# HandschuhPlatineFinal.net
KiCad netlist of a schematic drawn in EAGLE
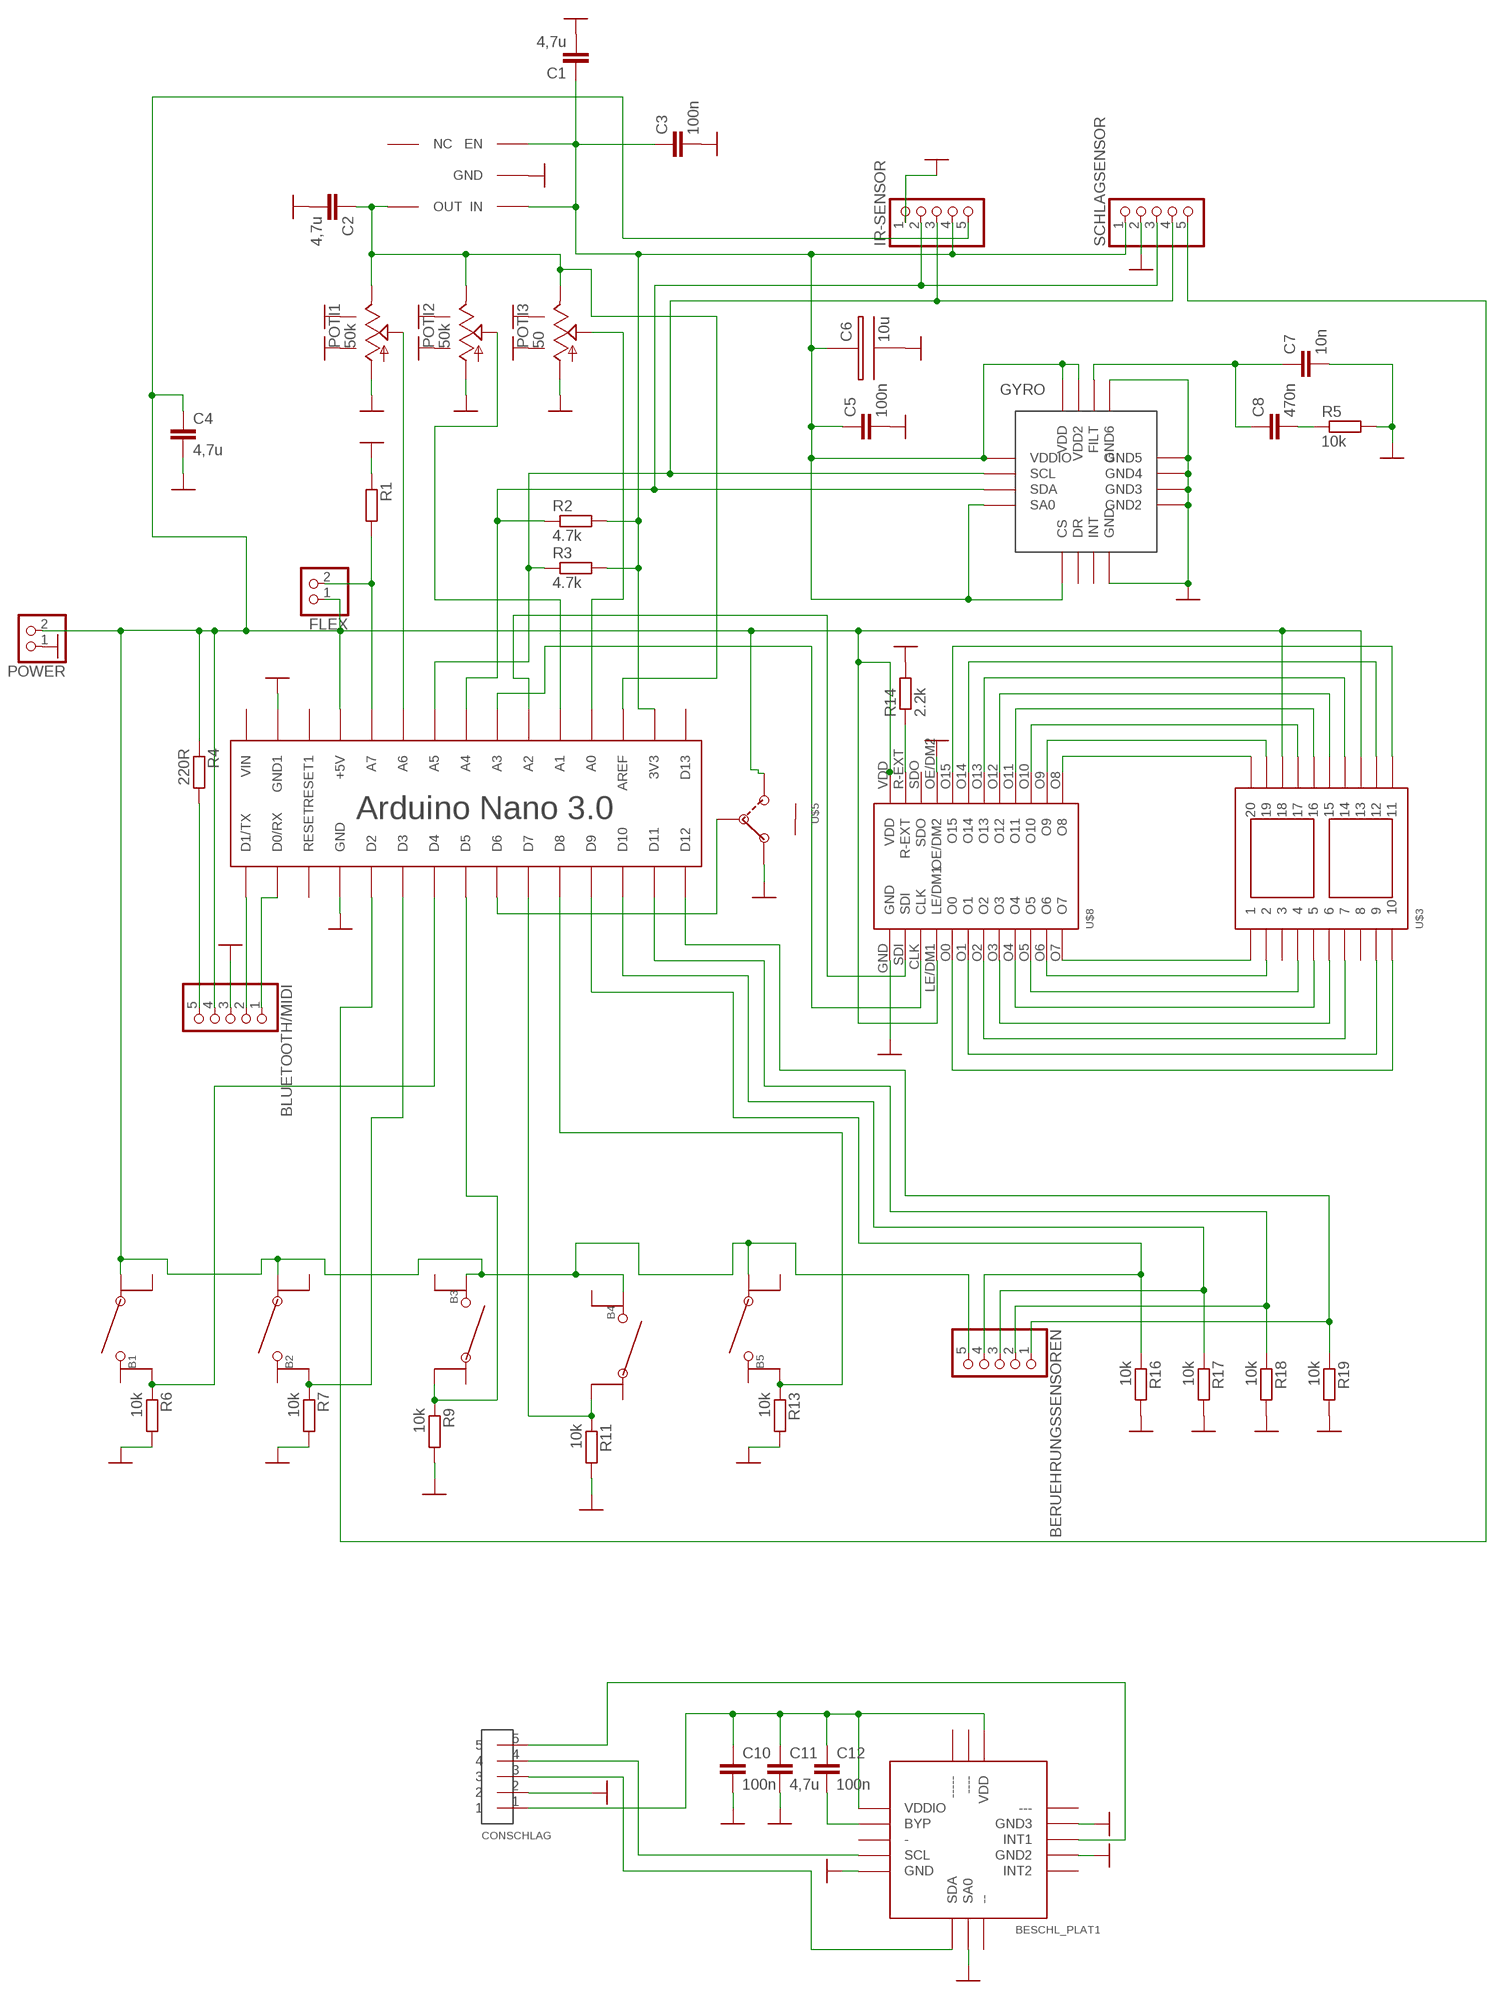
[diagram p0: schematic, sheet 1]

(export (version "E")
  (design (tool "Eeschema 10.0.6"))
  (components
    (comp (ref "B1")
      (value "BUTTON")
      (footprint "eagle-import:BUTTON")
      (libsource (lib "eagle-import") (part "BUTTON"))
    )
    (comp (ref "B2")
      (value "BUTTON")
      (footprint "eagle-import:BUTTON")
      (libsource (lib "eagle-import") (part "BUTTON"))
    )
    (comp (ref "B3")
      (value "BUTTON")
      (footprint "eagle-import:BUTTON")
      (libsource (lib "eagle-import") (part "BUTTON"))
    )
    (comp (ref "B4")
      (value "BUTTON")
      (footprint "eagle-import:BUTTON")
      (libsource (lib "eagle-import") (part "BUTTON"))
    )
    (comp (ref "B5")
      (value "BUTTON")
      (footprint "eagle-import:BUTTON")
      (libsource (lib "eagle-import") (part "BUTTON"))
    )
    (comp (ref "BERUEHRUNGSSENSOREN")
      (value "PINHD-1X5")
      (footprint "eagle-import:1X05")
      (libsource (lib "eagle-import") (part "PINHD-1X5"))
    )
    (comp (ref "BESCHL_PLAT1")
      (value "BESCHLEUNIGSUNGSSENSOR")
      (footprint "eagle-import:BESCHLEUNIGUNGSSENSOR")
      (libsource (lib "eagle-import") (part "BESCHLEUNIGSUNGSSENSOR"))
    )
    (comp (ref "BLUETOOTH/MIDI")
      (value "PINHD-1X5")
      (footprint "eagle-import:1X05")
      (libsource (lib "eagle-import") (part "PINHD-1X5"))
    )
    (comp (ref "C1")
      (value "4,7u")
      (footprint "eagle-import:C0805")
      (libsource (lib "eagle-import") (part "C-EUC0805"))
    )
    (comp (ref "C2")
      (value "4,7u")
      (footprint "eagle-import:C0805")
      (libsource (lib "eagle-import") (part "C-EUC0805"))
    )
    (comp (ref "C3")
      (value "100n")
      (footprint "eagle-import:C0805")
      (libsource (lib "eagle-import") (part "C-EUC0805"))
    )
    (comp (ref "C4")
      (value "4,7u")
      (footprint "eagle-import:C0805")
      (libsource (lib "eagle-import") (part "C-EUC0805"))
    )
    (comp (ref "C5")
      (value "100n")
      (footprint "eagle-import:C0805")
      (libsource (lib "eagle-import") (part "C-EUC0805"))
    )
    (comp (ref "C6")
      (value "10u")
      (footprint "eagle-import:22U-KONDENSATOR")
      (libsource (lib "eagle-import") (part "22U-KONDENSATOR"))
    )
    (comp (ref "C7")
      (value "10n")
      (footprint "eagle-import:C0805")
      (libsource (lib "eagle-import") (part "C-EUC0805"))
    )
    (comp (ref "C8")
      (value "470n")
      (footprint "eagle-import:C0805")
      (libsource (lib "eagle-import") (part "C-EUC0805"))
    )
    (comp (ref "C10")
      (value "100n")
      (footprint "eagle-import:C0805")
      (libsource (lib "eagle-import") (part "C-EUC0805"))
    )
    (comp (ref "C11")
      (value "4,7u")
      (footprint "eagle-import:C0805")
      (libsource (lib "eagle-import") (part "C-EUC0805"))
    )
    (comp (ref "C12")
      (value "100n")
      (footprint "eagle-import:C0805")
      (libsource (lib "eagle-import") (part "C-EUC0805"))
    )
    (comp (ref "CONSCHLAG")
      (value "BREAKBOARDCON2")
      (footprint "eagle-import:BREAKBOARDCON")
      (libsource (lib "eagle-import") (part "BREAKBOARDCON2"))
    )
    (comp (ref "FLEX")
      (value "PINHD-1X2")
      (footprint "eagle-import:1X02")
      (libsource (lib "eagle-import") (part "PINHD-1X2"))
    )
    (comp (ref "GYRO")
      (value "GYRO")
      (footprint "eagle-import:GYRO")
      (libsource (lib "eagle-import") (part "GYRO"))
    )
    (comp (ref "IR-SENSOR")
      (value "PINHD-1X5")
      (footprint "eagle-import:1X05")
      (libsource (lib "eagle-import") (part "PINHD-1X5"))
    )
    (comp (ref "POTI1")
      (value "50k")
      (footprint "eagle-import:POTI")
      (libsource (lib "eagle-import") (part "POTI"))
    )
    (comp (ref "POTI2")
      (value "50k")
      (footprint "eagle-import:POTI")
      (libsource (lib "eagle-import") (part "POTI"))
    )
    (comp (ref "POTI3")
      (value "50")
      (footprint "eagle-import:POTI")
      (libsource (lib "eagle-import") (part "POTI"))
    )
    (comp (ref "POWER")
      (value "PINHD-1X2")
      (footprint "eagle-import:1X02")
      (libsource (lib "eagle-import") (part "PINHD-1X2"))
    )
    (comp (ref "R1")
      (value "R-EU_M0805")
      (footprint "eagle-import:M0805")
      (libsource (lib "eagle-import") (part "R-EU_M0805"))
    )
    (comp (ref "R2")
      (value "4.7k")
      (footprint "eagle-import:M0805")
      (libsource (lib "eagle-import") (part "R-EU_M0805"))
    )
    (comp (ref "R3")
      (value "4.7k")
      (footprint "eagle-import:M0805")
      (libsource (lib "eagle-import") (part "R-EU_M0805"))
    )
    (comp (ref "R4")
      (value "220R")
      (footprint "eagle-import:M0805")
      (libsource (lib "eagle-import") (part "R-EU_M0805"))
    )
    (comp (ref "R5")
      (value "10k")
      (footprint "eagle-import:M0805")
      (libsource (lib "eagle-import") (part "R-EU_M0805"))
    )
    (comp (ref "R6")
      (value "10k")
      (footprint "eagle-import:M0805")
      (libsource (lib "eagle-import") (part "R-EU_M0805"))
    )
    (comp (ref "R7")
      (value "10k")
      (footprint "eagle-import:M0805")
      (libsource (lib "eagle-import") (part "R-EU_M0805"))
    )
    (comp (ref "R9")
      (value "10k")
      (footprint "eagle-import:M0805")
      (libsource (lib "eagle-import") (part "R-EU_M0805"))
    )
    (comp (ref "R11")
      (value "10k")
      (footprint "eagle-import:M0805")
      (libsource (lib "eagle-import") (part "R-EU_M0805"))
    )
    (comp (ref "R13")
      (value "10k")
      (footprint "eagle-import:M0805")
      (libsource (lib "eagle-import") (part "R-EU_M0805"))
    )
    (comp (ref "R14")
      (value "2.2k")
      (footprint "eagle-import:M0805")
      (libsource (lib "eagle-import") (part "R-EU_M0805"))
    )
    (comp (ref "R16")
      (value "10k")
      (footprint "eagle-import:M0805")
      (libsource (lib "eagle-import") (part "R-EU_M0805"))
    )
    (comp (ref "R17")
      (value "10k")
      (footprint "eagle-import:M0805")
      (libsource (lib "eagle-import") (part "R-EU_M0805"))
    )
    (comp (ref "R18")
      (value "10k")
      (footprint "eagle-import:M0805")
      (libsource (lib "eagle-import") (part "R-EU_M0805"))
    )
    (comp (ref "R19")
      (value "10k")
      (footprint "eagle-import:M0805")
      (libsource (lib "eagle-import") (part "R-EU_M0805"))
    )
    (comp (ref "SCHLAGSENSOR")
      (value "PINHD-1X5")
      (footprint "eagle-import:1X05")
      (libsource (lib "eagle-import") (part "PINHD-1X5"))
    )
    (comp (ref "U$2")
      (value "ARDUINONANO")
      (footprint "eagle-import:PDIP-32")
      (libsource (lib "eagle-import") (part "ARDUINONANO"))
    )
    (comp (ref "U$3")
      (value "7-SEGMENT")
      (footprint "eagle-import:7-SEGMENT")
      (libsource (lib "eagle-import") (part "7-SEGMENT"))
    )
    (comp (ref "U$4")
      (value "1,1V-SPANNUNGSREGLER")
      (footprint "eagle-import:1,1V-SPANNUNGSREGLER")
      (libsource (lib "eagle-import") (part "1,1V-SPANNUNGSREGLER"))
    )
    (comp (ref "U$5")
      (value "SCHALTER")
      (footprint "eagle-import:SCHALTER")
      (libsource (lib "eagle-import") (part "SCHALTER"))
    )
    (comp (ref "U$8")
      (value "7-SEGMENT-TREIBER")
      (footprint "eagle-import:7-SEGMENT-TREIBER")
      (libsource (lib "eagle-import") (part "7-SEGMENT-TREIBER"))
    )
  )
  (nets
    (net (code "1") (name "Net-(B1-Pad2)") (class "Default")
      (node (ref "B1") (pin "2") (pinfunction "2_2") (pintype "bidirectional"))
      (node (ref "R6") (pin "1") (pinfunction "1_1") (pintype "passive"))
      (node (ref "U$2") (pin "D4") (pinfunction "D4_D4") (pintype "bidirectional"))
    )
    (net (code "2") (name "Net-(B1-Pad3)") (class "Default")
      (node (ref "B1") (pin "3") (pinfunction "3_3") (pintype "bidirectional"))
      (node (ref "B2") (pin "3") (pinfunction "3_3") (pintype "bidirectional"))
      (node (ref "B3") (pin "1") (pinfunction "1_1") (pintype "bidirectional"))
      (node (ref "B4") (pin "1") (pinfunction "1_1") (pintype "bidirectional"))
      (node (ref "B5") (pin "3") (pinfunction "3_3") (pintype "bidirectional"))
      (node (ref "BERUEHRUNGSSENSOREN") (pin "5") (pinfunction "5_5") (pintype "passive"))
      (node (ref "BLUETOOTH/MIDI") (pin "4") (pinfunction "4_4") (pintype "passive"))
      (node (ref "C4") (pin "1") (pinfunction "1_1") (pintype "passive"))
      (node (ref "FLEX") (pin "1") (pinfunction "1_1") (pintype "passive"))
      (node (ref "IR-SENSOR") (pin "5") (pinfunction "5_5") (pintype "passive"))
      (node (ref "POWER") (pin "2") (pinfunction "2_2") (pintype "passive"))
      (node (ref "R4") (pin "1") (pinfunction "1_1") (pintype "passive"))
      (node (ref "U$2") (pin "+5V") (pinfunction "+5V_+5V") (pintype "bidirectional"))
      (node (ref "U$3") (pin "13") (pinfunction "13_13") (pintype "bidirectional"))
      (node (ref "U$3") (pin "18") (pinfunction "18_18") (pintype "bidirectional"))
      (node (ref "U$5") (pin "3") (pinfunction "3_3") (pintype "bidirectional"))
      (node (ref "U$8") (pin "LE/DM1") (pinfunction "LE/DM1_LE/DM1") (pintype "bidirectional"))
      (node (ref "U$8") (pin "VDD") (pinfunction "VDD_VDD") (pintype "bidirectional"))
    )
    (net (code "3") (name "Net-(B2-Pad2)") (class "Default")
      (node (ref "B2") (pin "2") (pinfunction "2_2") (pintype "bidirectional"))
      (node (ref "R7") (pin "1") (pinfunction "1_1") (pintype "passive"))
      (node (ref "U$2") (pin "D3") (pinfunction "D3_D3") (pintype "bidirectional"))
    )
    (net (code "4") (name "Net-(B3-Pad4)") (class "Default")
      (node (ref "B3") (pin "4") (pinfunction "4_4") (pintype "bidirectional"))
      (node (ref "R9") (pin "1") (pinfunction "1_1") (pintype "passive"))
      (node (ref "U$2") (pin "D5") (pinfunction "D5_D5") (pintype "bidirectional"))
    )
    (net (code "5") (name "Net-(B4-Pad4)") (class "Default")
      (node (ref "B4") (pin "4") (pinfunction "4_4") (pintype "bidirectional"))
      (node (ref "R11") (pin "1") (pinfunction "1_1") (pintype "passive"))
      (node (ref "U$2") (pin "D7") (pinfunction "D7_D7") (pintype "bidirectional"))
    )
    (net (code "6") (name "Net-(B5-Pad2)") (class "Default")
      (node (ref "B5") (pin "2") (pinfunction "2_2") (pintype "bidirectional"))
      (node (ref "R13") (pin "1") (pinfunction "1_1") (pintype "passive"))
      (node (ref "U$2") (pin "D8") (pinfunction "D8_D8") (pintype "bidirectional"))
    )
    (net (code "7") (name "Net-(BERUEHRUNGSSENSOREN-Pad1)") (class "Default")
      (node (ref "BERUEHRUNGSSENSOREN") (pin "1") (pinfunction "1_1") (pintype "passive"))
      (node (ref "R19") (pin "1") (pinfunction "1_1") (pintype "passive"))
      (node (ref "U$2") (pin "D12") (pinfunction "D12_D12") (pintype "bidirectional"))
    )
    (net (code "8") (name "Net-(BERUEHRUNGSSENSOREN-Pad2)") (class "Default")
      (node (ref "BERUEHRUNGSSENSOREN") (pin "2") (pinfunction "2_2") (pintype "passive"))
      (node (ref "R18") (pin "1") (pinfunction "1_1") (pintype "passive"))
      (node (ref "U$2") (pin "D11") (pinfunction "D11_D11") (pintype "bidirectional"))
    )
    (net (code "9") (name "Net-(BERUEHRUNGSSENSOREN-Pad3)") (class "Default")
      (node (ref "BERUEHRUNGSSENSOREN") (pin "3") (pinfunction "3_3") (pintype "passive"))
      (node (ref "R17") (pin "1") (pinfunction "1_1") (pintype "passive"))
      (node (ref "U$2") (pin "D10") (pinfunction "D10_D10") (pintype "bidirectional"))
    )
    (net (code "10") (name "Net-(BERUEHRUNGSSENSOREN-Pad4)") (class "Default")
      (node (ref "BERUEHRUNGSSENSOREN") (pin "4") (pinfunction "4_4") (pintype "passive"))
      (node (ref "R16") (pin "1") (pinfunction "1_1") (pintype "passive"))
      (node (ref "U$2") (pin "D9") (pinfunction "D9_D9") (pintype "bidirectional"))
    )
    (net (code "11") (name "Net-(BESCHL_PLAT1-PadBYP)") (class "Default")
      (node (ref "BESCHL_PLAT1") (pin "BYP") (pinfunction "BYP_BYP") (pintype "bidirectional"))
      (node (ref "C12") (pin "2") (pinfunction "2_2") (pintype "passive"))
    )
    (net (code "12") (name "Net-(BESCHL_PLAT1-PadINT1)") (class "Default")
      (node (ref "BESCHL_PLAT1") (pin "INT1") (pinfunction "INT1_INT1") (pintype "bidirectional"))
      (node (ref "CONSCHLAG") (pin "5") (pinfunction "5_5") (pintype "bidirectional"))
    )
    (net (code "13") (name "Net-(BESCHL_PLAT1-PadSCL)") (class "Default")
      (node (ref "BESCHL_PLAT1") (pin "SCL") (pinfunction "SCL_SCL") (pintype "bidirectional"))
      (node (ref "CONSCHLAG") (pin "4") (pinfunction "4_4") (pintype "bidirectional"))
    )
    (net (code "14") (name "Net-(BESCHL_PLAT1-PadSDA)") (class "Default")
      (node (ref "BESCHL_PLAT1") (pin "SDA") (pinfunction "SDA_SDA") (pintype "bidirectional"))
      (node (ref "CONSCHLAG") (pin "3") (pinfunction "3_3") (pintype "bidirectional"))
    )
    (net (code "15") (name "Net-(BESCHL_PLAT1-PadVDD)") (class "Default")
      (node (ref "BESCHL_PLAT1") (pin "VDD") (pinfunction "VDD_VDD") (pintype "bidirectional"))
      (node (ref "BESCHL_PLAT1") (pin "VDDIO") (pinfunction "VDDIO_VDDIO") (pintype "bidirectional"))
      (node (ref "C10") (pin "1") (pinfunction "1_1") (pintype "passive"))
      (node (ref "C11") (pin "1") (pinfunction "1_1") (pintype "passive"))
      (node (ref "C12") (pin "1") (pinfunction "1_1") (pintype "passive"))
      (node (ref "CONSCHLAG") (pin "1") (pinfunction "1_1") (pintype "bidirectional"))
    )
    (net (code "16") (name "Net-(BLUETOOTH/MIDI-Pad1)") (class "Default")
      (node (ref "BLUETOOTH/MIDI") (pin "1") (pinfunction "1_1") (pintype "passive"))
      (node (ref "U$2") (pin "D0/RX") (pinfunction "D0/RX_D0/RX") (pintype "bidirectional"))
    )
    (net (code "17") (name "Net-(BLUETOOTH/MIDI-Pad2)") (class "Default")
      (node (ref "BLUETOOTH/MIDI") (pin "2") (pinfunction "2_2") (pintype "passive"))
      (node (ref "U$2") (pin "D1/TX") (pinfunction "D1/TX_D1/TX") (pintype "bidirectional"))
    )
    (net (code "18") (name "Net-(BLUETOOTH/MIDI-Pad5)") (class "Default")
      (node (ref "BLUETOOTH/MIDI") (pin "5") (pinfunction "5_5") (pintype "passive"))
      (node (ref "R4") (pin "2") (pinfunction "2_2") (pintype "passive"))
    )
    (net (code "19") (name "Net-(C1-Pad1)") (class "Default")
      (node (ref "C1") (pin "1") (pinfunction "1_1") (pintype "passive"))
      (node (ref "C3") (pin "1") (pinfunction "1_1") (pintype "passive"))
      (node (ref "C5") (pin "1") (pinfunction "1_1") (pintype "passive"))
      (node (ref "C6") (pin "+") (pinfunction "+_+") (pintype "bidirectional"))
      (node (ref "GYRO") (pin "CS") (pinfunction "CS_CS") (pintype "bidirectional"))
      (node (ref "GYRO") (pin "SA0") (pinfunction "SA0_SA0") (pintype "bidirectional"))
      (node (ref "GYRO") (pin "VDD") (pinfunction "VDD_VDD") (pintype "bidirectional"))
      (node (ref "GYRO") (pin "VDD2") (pinfunction "VDD2_VDD2") (pintype "bidirectional"))
      (node (ref "GYRO") (pin "VDDIO") (pinfunction "VDDIO_VDDIO") (pintype "bidirectional"))
      (node (ref "IR-SENSOR") (pin "4") (pinfunction "4_4") (pintype "passive"))
      (node (ref "R2") (pin "2") (pinfunction "2_2") (pintype "passive"))
      (node (ref "R3") (pin "2") (pinfunction "2_2") (pintype "passive"))
      (node (ref "SCHLAGSENSOR") (pin "1") (pinfunction "1_1") (pintype "passive"))
      (node (ref "U$2") (pin "3V3") (pinfunction "3V3_3V3") (pintype "bidirectional"))
      (node (ref "U$4") (pin "EN") (pinfunction "EN_EN") (pintype "bidirectional"))
      (node (ref "U$4") (pin "IN") (pinfunction "IN_IN") (pintype "bidirectional"))
    )
    (net (code "20") (name "Net-(C2-Pad1)") (class "Default")
      (node (ref "C2") (pin "1") (pinfunction "1_1") (pintype "passive"))
      (node (ref "POTI1") (pin "VCC") (pinfunction "VCC_VCC") (pintype "passive"))
      (node (ref "POTI2") (pin "VCC") (pinfunction "VCC_VCC") (pintype "passive"))
      (node (ref "POTI3") (pin "VCC") (pinfunction "VCC_VCC") (pintype "passive"))
      (node (ref "U$2") (pin "AREF") (pinfunction "AREF_AREF") (pintype "bidirectional"))
      (node (ref "U$4") (pin "OUT") (pinfunction "OUT_OUT") (pintype "bidirectional"))
    )
    (net (code "21") (name "Net-(C7-Pad1)") (class "Default")
      (node (ref "C7") (pin "1") (pinfunction "1_1") (pintype "passive"))
      (node (ref "C8") (pin "1") (pinfunction "1_1") (pintype "passive"))
      (node (ref "GYRO") (pin "FILT") (pinfunction "FILT_FILT") (pintype "bidirectional"))
    )
    (net (code "22") (name "Net-(C8-Pad2)") (class "Default")
      (node (ref "C8") (pin "2") (pinfunction "2_2") (pintype "passive"))
      (node (ref "R5") (pin "1") (pinfunction "1_1") (pintype "passive"))
    )
    (net (code "23") (name "Net-(R14-Pad1)") (class "Default")
      (node (ref "R14") (pin "1") (pinfunction "1_1") (pintype "passive"))
      (node (ref "U$8") (pin "R-EXT") (pinfunction "R-EXT_R-EXT") (pintype "bidirectional"))
    )
    (net (code "24") (name "Net-(SCHLAGSENSOR-Pad5)") (class "Default")
      (node (ref "SCHLAGSENSOR") (pin "5") (pinfunction "5_5") (pintype "passive"))
      (node (ref "U$2") (pin "D2") (pinfunction "D2_D2") (pintype "bidirectional"))
    )
    (net (code "25") (name "Net-(U$2-A0)") (class "Default")
      (node (ref "POTI3") (pin "VALUE") (pinfunction "VALUE_VALUE") (pintype "passive"))
      (node (ref "U$2") (pin "A7") (pinfunction "A0_A7") (pintype "bidirectional"))
    )
    (net (code "26") (name "Net-(U$2-A1)") (class "Default")
      (node (ref "POTI2") (pin "VALUE") (pinfunction "VALUE_VALUE") (pintype "passive"))
      (node (ref "U$2") (pin "A6") (pinfunction "A1_A6") (pintype "bidirectional"))
    )
    (net (code "27") (name "Net-(U$2-A2)") (class "Default")
      (node (ref "U$2") (pin "A5") (pinfunction "A2_A5") (pintype "bidirectional"))
      (node (ref "U$8") (pin "SDI") (pinfunction "SDI_SDI") (pintype "bidirectional"))
    )
    (net (code "28") (name "Net-(U$2-A3)") (class "Default")
      (node (ref "U$2") (pin "A4") (pinfunction "A3_A4") (pintype "bidirectional"))
      (node (ref "U$8") (pin "CLK") (pinfunction "CLK_CLK") (pintype "bidirectional"))
    )
    (net (code "29") (name "Net-(U$2-A4)") (class "Default")
      (node (ref "GYRO") (pin "SDA") (pinfunction "SDA_SDA") (pintype "bidirectional"))
      (node (ref "IR-SENSOR") (pin "2") (pinfunction "2_2") (pintype "passive"))
      (node (ref "R2") (pin "1") (pinfunction "1_1") (pintype "passive"))
      (node (ref "SCHLAGSENSOR") (pin "3") (pinfunction "3_3") (pintype "passive"))
      (node (ref "U$2") (pin "A3") (pinfunction "A4_A3") (pintype "bidirectional"))
    )
    (net (code "30") (name "Net-(U$2-A5)") (class "Default")
      (node (ref "GYRO") (pin "SCL") (pinfunction "SCL_SCL") (pintype "bidirectional"))
      (node (ref "IR-SENSOR") (pin "3") (pinfunction "3_3") (pintype "passive"))
      (node (ref "R3") (pin "1") (pinfunction "1_1") (pintype "passive"))
      (node (ref "SCHLAGSENSOR") (pin "4") (pinfunction "4_4") (pintype "passive"))
      (node (ref "U$2") (pin "A2") (pinfunction "A5_A2") (pintype "bidirectional"))
    )
    (net (code "31") (name "Net-(U$2-A6)") (class "Default")
      (node (ref "POTI1") (pin "VALUE") (pinfunction "VALUE_VALUE") (pintype "passive"))
      (node (ref "U$2") (pin "A1") (pinfunction "A6_A1") (pintype "bidirectional"))
    )
    (net (code "32") (name "Net-(U$2-A7)") (class "Default")
      (node (ref "FLEX") (pin "2") (pinfunction "2_2") (pintype "passive"))
      (node (ref "R1") (pin "2") (pinfunction "2_2") (pintype "passive"))
      (node (ref "U$2") (pin "A0") (pinfunction "A7_A0") (pintype "bidirectional"))
    )
    (net (code "33") (name "Net-(U$2-PadD6)") (class "Default")
      (node (ref "U$2") (pin "D6") (pinfunction "D6_D6") (pintype "bidirectional"))
      (node (ref "U$5") (pin "2") (pinfunction "2_2") (pintype "bidirectional"))
    )
    (net (code "34") (name "Net-(U$3-Pad1)") (class "Default")
      (node (ref "U$3") (pin "1") (pinfunction "1_1") (pintype "bidirectional"))
      (node (ref "U$8") (pin "O7") (pinfunction "O7_O7") (pintype "bidirectional"))
    )
    (net (code "35") (name "Net-(U$3-Pad2)") (class "Default")
      (node (ref "U$3") (pin "2") (pinfunction "2_2") (pintype "bidirectional"))
      (node (ref "U$8") (pin "O6") (pinfunction "O6_O6") (pintype "bidirectional"))
    )
    (net (code "36") (name "Net-(U$3-Pad4)") (class "Default")
      (node (ref "U$3") (pin "4") (pinfunction "4_4") (pintype "bidirectional"))
      (node (ref "U$8") (pin "O5") (pinfunction "O5_O5") (pintype "bidirectional"))
    )
    (net (code "37") (name "Net-(U$3-Pad5)") (class "Default")
      (node (ref "U$3") (pin "5") (pinfunction "5_5") (pintype "bidirectional"))
      (node (ref "U$8") (pin "O4") (pinfunction "O4_O4") (pintype "bidirectional"))
    )
    (net (code "38") (name "Net-(U$3-Pad6)") (class "Default")
      (node (ref "U$3") (pin "6") (pinfunction "6_6") (pintype "bidirectional"))
      (node (ref "U$8") (pin "O3") (pinfunction "O3_O3") (pintype "bidirectional"))
    )
    (net (code "39") (name "Net-(U$3-Pad7)") (class "Default")
      (node (ref "U$3") (pin "7") (pinfunction "7_7") (pintype "bidirectional"))
      (node (ref "U$8") (pin "O2") (pinfunction "O2_O2") (pintype "bidirectional"))
    )
    (net (code "40") (name "Net-(U$3-Pad9)") (class "Default")
      (node (ref "U$3") (pin "9") (pinfunction "9_9") (pintype "bidirectional"))
      (node (ref "U$8") (pin "O1") (pinfunction "O1_O1") (pintype "bidirectional"))
    )
    (net (code "41") (name "Net-(U$3-Pad10)") (class "Default")
      (node (ref "U$3") (pin "10") (pinfunction "10_10") (pintype "bidirectional"))
      (node (ref "U$8") (pin "O0") (pinfunction "O0_O0") (pintype "bidirectional"))
    )
    (net (code "42") (name "Net-(U$3-Pad11)") (class "Default")
      (node (ref "U$3") (pin "11") (pinfunction "11_11") (pintype "bidirectional"))
      (node (ref "U$8") (pin "O15") (pinfunction "O15_O15") (pintype "bidirectional"))
    )
    (net (code "43") (name "Net-(U$3-Pad12)") (class "Default")
      (node (ref "U$3") (pin "12") (pinfunction "12_12") (pintype "bidirectional"))
      (node (ref "U$8") (pin "O14") (pinfunction "O14_O14") (pintype "bidirectional"))
    )
    (net (code "44") (name "Net-(U$3-Pad14)") (class "Default")
      (node (ref "U$3") (pin "14") (pinfunction "14_14") (pintype "bidirectional"))
      (node (ref "U$8") (pin "O13") (pinfunction "O13_O13") (pintype "bidirectional"))
    )
    (net (code "45") (name "Net-(U$3-Pad15)") (class "Default")
      (node (ref "U$3") (pin "15") (pinfunction "15_15") (pintype "bidirectional"))
      (node (ref "U$8") (pin "O12") (pinfunction "O12_O12") (pintype "bidirectional"))
    )
    (net (code "46") (name "Net-(U$3-Pad16)") (class "Default")
      (node (ref "U$3") (pin "16") (pinfunction "16_16") (pintype "bidirectional"))
      (node (ref "U$8") (pin "O11") (pinfunction "O11_O11") (pintype "bidirectional"))
    )
    (net (code "47") (name "Net-(U$3-Pad17)") (class "Default")
      (node (ref "U$3") (pin "17") (pinfunction "17_17") (pintype "bidirectional"))
      (node (ref "U$8") (pin "O10") (pinfunction "O10_O10") (pintype "bidirectional"))
    )
    (net (code "48") (name "Net-(U$3-Pad19)") (class "Default")
      (node (ref "U$3") (pin "19") (pinfunction "19_19") (pintype "bidirectional"))
      (node (ref "U$8") (pin "O9") (pinfunction "O9_O9") (pintype "bidirectional"))
    )
    (net (code "49") (name "Net-(U$3-Pad20)") (class "Default")
      (node (ref "U$3") (pin "20") (pinfunction "20_20") (pintype "bidirectional"))
      (node (ref "U$8") (pin "O8") (pinfunction "O8_O8") (pintype "bidirectional"))
    )
    (net (code "50") (name "POWER_SUPPLY1_GND") (class "Default")
      (node (ref "BESCHL_PLAT1") (pin "GND") (pinfunction "GND_GND") (pintype "bidirectional"))
      (node (ref "BESCHL_PLAT1") (pin "GND2") (pinfunction "GND2_GND2") (pintype "bidirectional"))
      (node (ref "BESCHL_PLAT1") (pin "GND3") (pinfunction "GND3_GND3") (pintype "bidirectional"))
      (node (ref "BESCHL_PLAT1") (pin "SA0") (pinfunction "SA0_SA0") (pintype "bidirectional"))
      (node (ref "BLUETOOTH/MIDI") (pin "3") (pinfunction "3_3") (pintype "passive"))
      (node (ref "C1") (pin "2") (pinfunction "2_2") (pintype "passive"))
      (node (ref "C10") (pin "2") (pinfunction "2_2") (pintype "passive"))
      (node (ref "C11") (pin "2") (pinfunction "2_2") (pintype "passive"))
      (node (ref "C2") (pin "2") (pinfunction "2_2") (pintype "passive"))
      (node (ref "C3") (pin "2") (pinfunction "2_2") (pintype "passive"))
      (node (ref "C4") (pin "2") (pinfunction "2_2") (pintype "passive"))
      (node (ref "C5") (pin "2") (pinfunction "2_2") (pintype "passive"))
      (node (ref "C6") (pin "-") (pinfunction "-_-") (pintype "bidirectional"))
      (node (ref "C7") (pin "2") (pinfunction "2_2") (pintype "passive"))
      (node (ref "CONSCHLAG") (pin "2") (pinfunction "2_2") (pintype "bidirectional"))
      (node (ref "GYRO") (pin "GND") (pinfunction "GND_GND") (pintype "bidirectional"))
      (node (ref "GYRO") (pin "GND2") (pinfunction "GND2_GND2") (pintype "bidirectional"))
      (node (ref "GYRO") (pin "GND3") (pinfunction "GND3_GND3") (pintype "bidirectional"))
      (node (ref "GYRO") (pin "GND4") (pinfunction "GND4_GND4") (pintype "bidirectional"))
      (node (ref "GYRO") (pin "GND5") (pinfunction "GND5_GND5") (pintype "bidirectional"))
      (node (ref "GYRO") (pin "GND6") (pinfunction "GND6_GND6") (pintype "bidirectional"))
      (node (ref "IR-SENSOR") (pin "1") (pinfunction "1_1") (pintype "passive"))
      (node (ref "POTI1") (pin "FIX1") (pinfunction "FUSS1_FIX1") (pintype "passive"))
      (node (ref "POTI1") (pin "FIX2") (pinfunction "FUSS2_FIX2") (pintype "passive"))
      (node (ref "POTI1") (pin "GND") (pinfunction "GND_GND") (pintype "passive"))
      (node (ref "POTI2") (pin "FIX1") (pinfunction "FUSS1_FIX1") (pintype "passive"))
      (node (ref "POTI2") (pin "FIX2") (pinfunction "FUSS2_FIX2") (pintype "passive"))
      (node (ref "POTI2") (pin "GND") (pinfunction "GND_GND") (pintype "passive"))
      (node (ref "POTI3") (pin "FIX1") (pinfunction "FUSS1_FIX1") (pintype "passive"))
      (node (ref "POTI3") (pin "FIX2") (pinfunction "FUSS2_FIX2") (pintype "passive"))
      (node (ref "POTI3") (pin "GND") (pinfunction "GND_GND") (pintype "passive"))
      (node (ref "POWER") (pin "1") (pinfunction "1_1") (pintype "passive"))
      (node (ref "R1") (pin "1") (pinfunction "1_1") (pintype "passive"))
      (node (ref "R11") (pin "2") (pinfunction "2_2") (pintype "passive"))
      (node (ref "R13") (pin "2") (pinfunction "2_2") (pintype "passive"))
      (node (ref "R14") (pin "2") (pinfunction "2_2") (pintype "passive"))
      (node (ref "R16") (pin "2") (pinfunction "2_2") (pintype "passive"))
      (node (ref "R17") (pin "2") (pinfunction "2_2") (pintype "passive"))
      (node (ref "R18") (pin "2") (pinfunction "2_2") (pintype "passive"))
      (node (ref "R19") (pin "2") (pinfunction "2_2") (pintype "passive"))
      (node (ref "R5") (pin "2") (pinfunction "2_2") (pintype "passive"))
      (node (ref "R6") (pin "2") (pinfunction "2_2") (pintype "passive"))
      (node (ref "R7") (pin "2") (pinfunction "2_2") (pintype "passive"))
      (node (ref "R9") (pin "2") (pinfunction "2_2") (pintype "passive"))
      (node (ref "SCHLAGSENSOR") (pin "2") (pinfunction "2_2") (pintype "passive"))
      (node (ref "U$2") (pin "GND") (pinfunction "GND_GND") (pintype "bidirectional"))
      (node (ref "U$2") (pin "GND1") (pinfunction "GND1_GND1") (pintype "bidirectional"))
      (node (ref "U$4") (pin "GND") (pinfunction "GND_GND") (pintype "bidirectional"))
      (node (ref "U$5") (pin "1") (pinfunction "1_1") (pintype "bidirectional"))
      (node (ref "U$8") (pin "GND") (pinfunction "GND_GND") (pintype "bidirectional"))
      (node (ref "U$8") (pin "OE/DM2") (pinfunction "OE/DM2_OE/DM2") (pintype "bidirectional"))
    )
    (net (code "51") (name "unconnected-(B1-Pad1)") (class "Default")
      (node (ref "B1") (pin "1") (pinfunction "1_1") (pintype "bidirectional"))
    )
    (net (code "52") (name "unconnected-(B1-Pad4)") (class "Default")
      (node (ref "B1") (pin "4") (pinfunction "4_4") (pintype "bidirectional"))
    )
    (net (code "53") (name "unconnected-(B2-Pad1)") (class "Default")
      (node (ref "B2") (pin "1") (pinfunction "1_1") (pintype "bidirectional"))
    )
    (net (code "54") (name "unconnected-(B2-Pad4)") (class "Default")
      (node (ref "B2") (pin "4") (pinfunction "4_4") (pintype "bidirectional"))
    )
    (net (code "55") (name "unconnected-(B3-Pad2)") (class "Default")
      (node (ref "B3") (pin "2") (pinfunction "2_2") (pintype "bidirectional"))
    )
    (net (code "56") (name "unconnected-(B3-Pad3)") (class "Default")
      (node (ref "B3") (pin "3") (pinfunction "3_3") (pintype "bidirectional"))
    )
    (net (code "57") (name "unconnected-(B4-Pad2)") (class "Default")
      (node (ref "B4") (pin "2") (pinfunction "2_2") (pintype "bidirectional"))
    )
    (net (code "58") (name "unconnected-(B4-Pad3)") (class "Default")
      (node (ref "B4") (pin "3") (pinfunction "3_3") (pintype "bidirectional"))
    )
    (net (code "59") (name "unconnected-(B5-Pad1)") (class "Default")
      (node (ref "B5") (pin "1") (pinfunction "1_1") (pintype "bidirectional"))
    )
    (net (code "60") (name "unconnected-(B5-Pad4)") (class "Default")
      (node (ref "B5") (pin "4") (pinfunction "4_4") (pintype "bidirectional"))
    )
    (net (code "61") (name "unconnected-(BESCHL_PLAT1-Pad-)") (class "Default")
      (node (ref "BESCHL_PLAT1") (pin "-") (pinfunction "-_-") (pintype "bidirectional"))
    )
    (net (code "62") (name "unconnected-(BESCHL_PLAT1-Pad--)") (class "Default")
      (node (ref "BESCHL_PLAT1") (pin "--") (pinfunction "--_--") (pintype "bidirectional"))
    )
    (net (code "63") (name "unconnected-(BESCHL_PLAT1-Pad---)") (class "Default")
      (node (ref "BESCHL_PLAT1") (pin "---") (pinfunction "---_---") (pintype "bidirectional"))
    )
    (net (code "64") (name "unconnected-(BESCHL_PLAT1-Pad----)") (class "Default")
      (node (ref "BESCHL_PLAT1") (pin "----") (pinfunction "----_----") (pintype "bidirectional"))
    )
    (net (code "65") (name "unconnected-(BESCHL_PLAT1-Pad-----)") (class "Default")
      (node (ref "BESCHL_PLAT1") (pin "-----") (pinfunction "-----_-----") (pintype "bidirectional"))
    )
    (net (code "66") (name "unconnected-(BESCHL_PLAT1-PadINT2)") (class "Default")
      (node (ref "BESCHL_PLAT1") (pin "INT2") (pinfunction "INT2_INT2") (pintype "bidirectional"))
    )
    (net (code "67") (name "unconnected-(GYRO-PadDR)") (class "Default")
      (node (ref "GYRO") (pin "DR") (pinfunction "DR_DR") (pintype "bidirectional"))
    )
    (net (code "68") (name "unconnected-(GYRO-PadINT)") (class "Default")
      (node (ref "GYRO") (pin "INT") (pinfunction "INT_INT") (pintype "bidirectional"))
    )
    (net (code "69") (name "unconnected-(U$2-PadD13)") (class "Default")
      (node (ref "U$2") (pin "D13") (pinfunction "D13_D13") (pintype "bidirectional"))
    )
    (net (code "70") (name "unconnected-(U$2-PadRESET)") (class "Default")
      (node (ref "U$2") (pin "RESET") (pinfunction "RESET_RESET") (pintype "bidirectional"))
    )
    (net (code "71") (name "unconnected-(U$2-PadRESET1)") (class "Default")
      (node (ref "U$2") (pin "RESET1") (pinfunction "RESET1_RESET1") (pintype "bidirectional"))
    )
    (net (code "72") (name "unconnected-(U$2-PadVIN)") (class "Default")
      (node (ref "U$2") (pin "VIN") (pinfunction "VIN_VIN") (pintype "bidirectional"))
    )
    (net (code "73") (name "unconnected-(U$3-Pad3)") (class "Default")
      (node (ref "U$3") (pin "3") (pinfunction "3_3") (pintype "bidirectional"))
    )
    (net (code "74") (name "unconnected-(U$3-Pad8)") (class "Default")
      (node (ref "U$3") (pin "8") (pinfunction "8_8") (pintype "bidirectional"))
    )
    (net (code "75") (name "unconnected-(U$4-PadNC)") (class "Default")
      (node (ref "U$4") (pin "NC") (pinfunction "NC_NC") (pintype "bidirectional"))
    )
    (net (code "76") (name "unconnected-(U$5-Pad4)") (class "Default")
      (node (ref "U$5") (pin "4") (pinfunction "4_4") (pintype "bidirectional"))
    )
    (net (code "77") (name "unconnected-(U$5-Pad5)") (class "Default")
      (node (ref "U$5") (pin "5") (pinfunction "5_5") (pintype "bidirectional"))
    )
    (net (code "78") (name "unconnected-(U$8-PadSDO)") (class "Default")
      (node (ref "U$8") (pin "SDO") (pinfunction "SDO_SDO") (pintype "bidirectional"))
    )
  )
)
